# room-therm.net
KiCad netlist of a schematic drawn in EAGLE
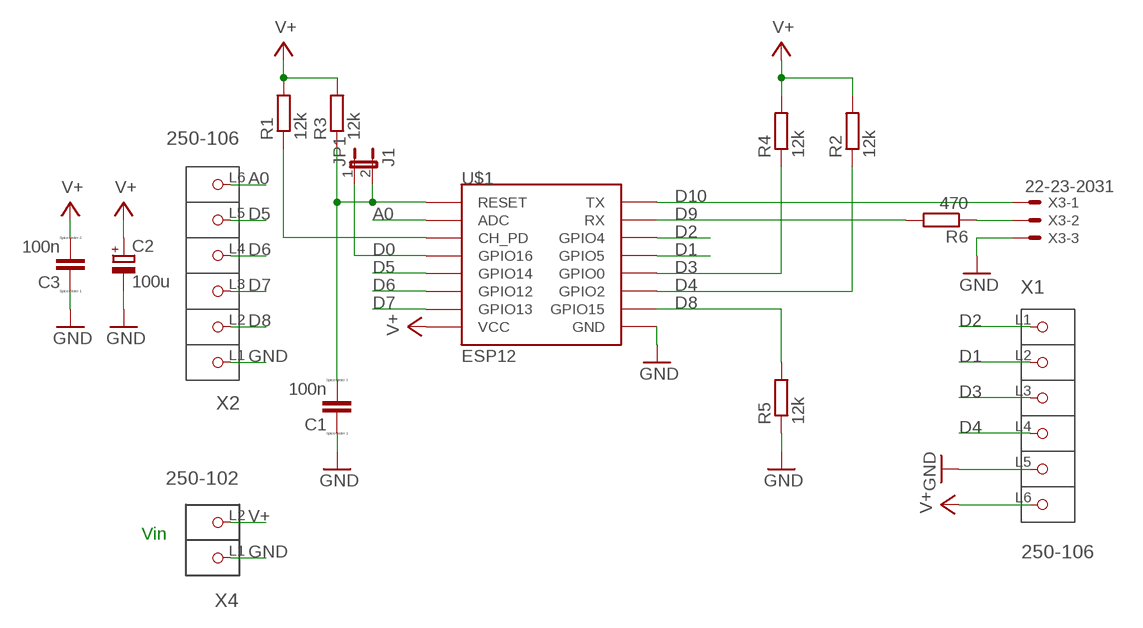
[diagram p0: schematic, sheet 1]

(export (version "E")
  (design (tool "Eeschema 10.0.6"))
  (components
    (comp (ref "C1")
      (value "100n")
      (footprint "eagle-import:C1005")
      (libsource (lib "eagle-import") (part "CC1005"))
    )
    (comp (ref "C2")
      (value "100u")
      (footprint "eagle-import:E2-4")
      (libsource (lib "eagle-import") (part "CPOL-EUE2-4"))
    )
    (comp (ref "C3")
      (value "100n")
      (footprint "eagle-import:C1005")
      (libsource (lib "eagle-import") (part "CC1005"))
    )
    (comp (ref "JP1")
      (value "J1")
      (footprint "eagle-import:JP1")
      (libsource (lib "eagle-import") (part "JP1E"))
    )
    (comp (ref "R1")
      (value "12k")
      (footprint "eagle-import:R0805")
      (libsource (lib "eagle-import") (part "R-EU_R0805"))
    )
    (comp (ref "R2")
      (value "12k")
      (footprint "eagle-import:R0805")
      (libsource (lib "eagle-import") (part "R-EU_R0805"))
    )
    (comp (ref "R3")
      (value "12k")
      (footprint "eagle-import:R0805")
      (libsource (lib "eagle-import") (part "R-EU_R0805"))
    )
    (comp (ref "R4")
      (value "12k")
      (footprint "eagle-import:R0805")
      (libsource (lib "eagle-import") (part "R-EU_R0805"))
    )
    (comp (ref "R5")
      (value "12k")
      (footprint "eagle-import:R0805")
      (libsource (lib "eagle-import") (part "R-EU_R0805"))
    )
    (comp (ref "R6")
      (value "470")
      (footprint "eagle-import:R0805")
      (libsource (lib "eagle-import") (part "R-EU_R0805"))
    )
    (comp (ref "U$1")
      (value "ESP12")
      (footprint "eagle-import:ESP12")
      (libsource (lib "eagle-import") (part "ESP12"))
    )
    (comp (ref "X1")
      (value "250-106")
      (footprint "eagle-import:P-250-106")
      (libsource (lib "eagle-import") (part "250-106"))
    )
    (comp (ref "X2")
      (value "250-106")
      (footprint "eagle-import:P-250-106")
      (libsource (lib "eagle-import") (part "250-106"))
    )
    (comp (ref "X3")
      (value "22-23-2031")
      (footprint "eagle-import:22-23-2031")
      (fields (field (name "MF") "MOLEX"))
      (libsource (lib "eagle-import") (part "22-23-2031"))
    )
    (comp (ref "X4")
      (value "250-102")
      (footprint "eagle-import:P-250-102")
      (libsource (lib "eagle-import") (part "250-102"))
    )
  )
  (nets
    (net (code "1") (name "/A0") (class "Default")
      (node (ref "U$1") (pin "ADC") (pinfunction "ADC_ADC") (pintype "bidirectional"))
      (node (ref "X2") (pin "L6") (pinfunction "P6_L6") (pintype "bidirectional"))
    )
    (net (code "2") (name "/D0") (class "Default")
      (node (ref "JP1") (pin "1") (pinfunction "1_1") (pintype "passive"))
      (node (ref "U$1") (pin "GPIO16") (pinfunction "GPIO16_GPIO16") (pintype "bidirectional"))
    )
    (net (code "3") (name "/D1") (class "Default")
      (node (ref "U$1") (pin "GPIO5") (pinfunction "GPIO5_GPIO5") (pintype "bidirectional"))
      (node (ref "X1") (pin "L2") (pinfunction "P2_L2") (pintype "bidirectional"))
    )
    (net (code "4") (name "/D2") (class "Default")
      (node (ref "U$1") (pin "GPIO4") (pinfunction "GPIO4_GPIO4") (pintype "bidirectional"))
      (node (ref "X1") (pin "L1") (pinfunction "P1_L1") (pintype "bidirectional"))
    )
    (net (code "5") (name "/D3") (class "Default")
      (node (ref "R4") (pin "1") (pinfunction "1_1") (pintype "passive"))
      (node (ref "U$1") (pin "GPIO0") (pinfunction "GPIO0_GPIO0") (pintype "bidirectional"))
      (node (ref "X1") (pin "L3") (pinfunction "P3_L3") (pintype "bidirectional"))
    )
    (net (code "6") (name "/D4") (class "Default")
      (node (ref "R2") (pin "1") (pinfunction "1_1") (pintype "passive"))
      (node (ref "U$1") (pin "GPIO2") (pinfunction "GPIO2_GPIO2") (pintype "bidirectional"))
      (node (ref "X1") (pin "L4") (pinfunction "P4_L4") (pintype "bidirectional"))
    )
    (net (code "7") (name "/D5") (class "Default")
      (node (ref "U$1") (pin "GPIO14") (pinfunction "GPIO14_GPIO14") (pintype "bidirectional"))
      (node (ref "X2") (pin "L5") (pinfunction "P5_L5") (pintype "bidirectional"))
    )
    (net (code "8") (name "/D6") (class "Default")
      (node (ref "U$1") (pin "GPIO12") (pinfunction "GPIO12_GPIO12") (pintype "bidirectional"))
      (node (ref "X2") (pin "L4") (pinfunction "P4_L4") (pintype "bidirectional"))
    )
    (net (code "9") (name "/D7") (class "Default")
      (node (ref "U$1") (pin "GPIO13") (pinfunction "GPIO13_GPIO13") (pintype "bidirectional"))
      (node (ref "X2") (pin "L3") (pinfunction "P3_L3") (pintype "bidirectional"))
    )
    (net (code "10") (name "/D8") (class "Default")
      (node (ref "R5") (pin "2") (pinfunction "2_2") (pintype "passive"))
      (node (ref "U$1") (pin "GPIO15") (pinfunction "GPIO15_GPIO15") (pintype "bidirectional"))
      (node (ref "X2") (pin "L2") (pinfunction "P2_L2") (pintype "bidirectional"))
    )
    (net (code "11") (name "/D9") (class "Default")
      (node (ref "R6") (pin "2") (pinfunction "2_2") (pintype "passive"))
      (node (ref "U$1") (pin "RX") (pinfunction "RX_RX") (pintype "bidirectional"))
    )
    (net (code "12") (name "/D10") (class "Default")
      (node (ref "U$1") (pin "TX") (pinfunction "TX_TX") (pintype "bidirectional"))
      (node (ref "X3") (pin "1") (pinfunction "S_1") (pintype "passive"))
    )
    (net (code "13") (name "GND") (class "Default")
      (node (ref "C1") (pin "1") (pinfunction "1_1") (pintype "passive"))
      (node (ref "C2") (pin "-") (pinfunction "-_-") (pintype "passive"))
      (node (ref "C3") (pin "1") (pinfunction "1_1") (pintype "passive"))
      (node (ref "R5") (pin "1") (pinfunction "1_1") (pintype "passive"))
      (node (ref "U$1") (pin "GND") (pinfunction "GND_GND") (pintype "bidirectional"))
      (node (ref "X1") (pin "L5") (pinfunction "P5_L5") (pintype "bidirectional"))
      (node (ref "X2") (pin "L1") (pinfunction "P1_L1") (pintype "bidirectional"))
      (node (ref "X3") (pin "3") (pinfunction "S_3") (pintype "passive"))
      (node (ref "X4") (pin "L1") (pinfunction "P1_L1") (pintype "bidirectional"))
    )
    (net (code "14") (name "Net-(C1-Pad2)") (class "Default")
      (node (ref "C1") (pin "2") (pinfunction "2_2") (pintype "passive"))
      (node (ref "JP1") (pin "2") (pinfunction "2_2") (pintype "passive"))
      (node (ref "R3") (pin "1") (pinfunction "1_1") (pintype "passive"))
      (node (ref "U$1") (pin "RESET") (pinfunction "RESET_RESET") (pintype "bidirectional"))
    )
    (net (code "15") (name "Net-(R1-Pad1)") (class "Default")
      (node (ref "R1") (pin "1") (pinfunction "1_1") (pintype "passive"))
      (node (ref "U$1") (pin "CH_PD") (pinfunction "CH_PD_CH_PD") (pintype "bidirectional"))
    )
    (net (code "16") (name "Net-(X3B-S)") (class "Default")
      (node (ref "R6") (pin "1") (pinfunction "1_1") (pintype "passive"))
      (node (ref "X3") (pin "2") (pinfunction "S_2") (pintype "passive"))
    )
    (net (code "17") (name "V+") (class "Default")
      (node (ref "C2") (pin "+") (pinfunction "+_+") (pintype "passive"))
      (node (ref "C3") (pin "2") (pinfunction "2_2") (pintype "passive"))
      (node (ref "R1") (pin "2") (pinfunction "2_2") (pintype "passive"))
      (node (ref "R2") (pin "2") (pinfunction "2_2") (pintype "passive"))
      (node (ref "R3") (pin "2") (pinfunction "2_2") (pintype "passive"))
      (node (ref "R4") (pin "2") (pinfunction "2_2") (pintype "passive"))
      (node (ref "U$1") (pin "VCC") (pinfunction "VCC_VCC") (pintype "bidirectional"))
      (node (ref "X1") (pin "L6") (pinfunction "P6_L6") (pintype "bidirectional"))
      (node (ref "X4") (pin "L2") (pinfunction "P2_L2") (pintype "bidirectional"))
    )
  )
)
